# MHI-AC-Ctrl_v1_1.net
KiCad netlist of a schematic drawn in EAGLE
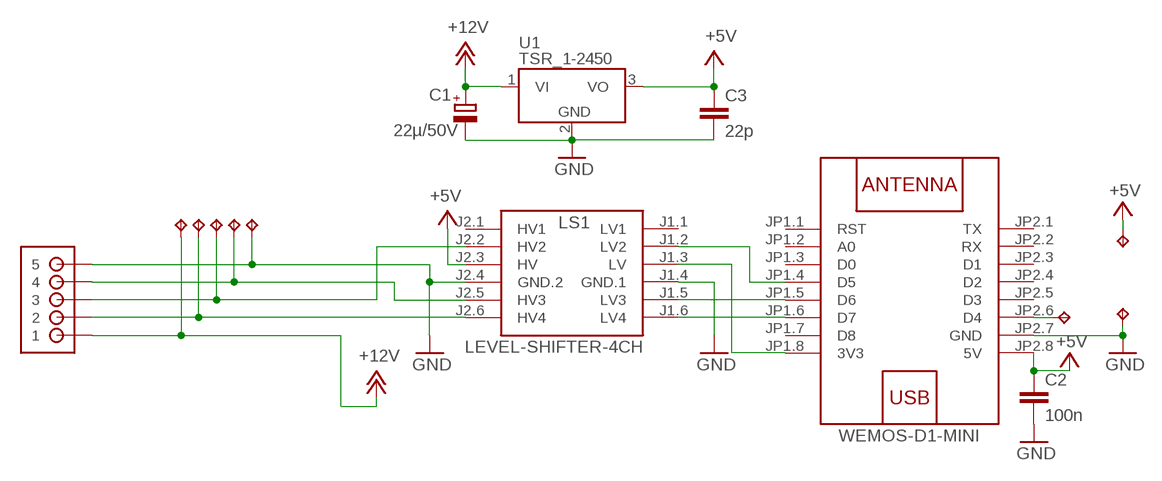
[diagram p0: schematic, sheet 1]

(export (version "E")
  (design (tool "Eeschema 10.0.6"))
  (components
    (comp (ref "C1")
      (value "22µ/50V")
      (footprint "eagle-import:E5-10,5")
      (libsource (lib "eagle-import") (part "CPOL-EUE5-10.5"))
    )
    (comp (ref "C2")
      (value "100n")
      (footprint "eagle-import:C025-024X044")
      (libsource (lib "eagle-import") (part "C-EU025-024X044"))
    )
    (comp (ref "C3")
      (value "22p")
      (footprint "eagle-import:C025-024X044")
      (libsource (lib "eagle-import") (part "C-EU025-024X044"))
    )
    (comp (ref "LS1")
      (value "LEVEL-SHIFTER-4CH")
      (footprint "eagle-import:LEVEL-SHIFTER-4CH")
      (libsource (lib "eagle-import") (part "LEVEL-SHIFTER-4CH"))
    )
    (comp (ref "TP6")
      (value "TPPAD1-13")
      (footprint "eagle-import:P1-13")
      (libsource (lib "eagle-import") (part "TPPAD1-13"))
    )
    (comp (ref "TP7")
      (value "TPPAD1-13")
      (footprint "eagle-import:P1-13")
      (libsource (lib "eagle-import") (part "TPPAD1-13"))
    )
    (comp (ref "TP8")
      (value "TPPAD1-13")
      (footprint "eagle-import:P1-13")
      (libsource (lib "eagle-import") (part "TPPAD1-13"))
    )
    (comp (ref "TP9")
      (value "TPPAD1-13")
      (footprint "eagle-import:P1-13")
      (libsource (lib "eagle-import") (part "TPPAD1-13"))
    )
    (comp (ref "TP10")
      (value "TPPAD1-13")
      (footprint "eagle-import:P1-13")
      (libsource (lib "eagle-import") (part "TPPAD1-13"))
    )
    (comp (ref "TP11")
      (value "TPPAD1-13")
      (footprint "eagle-import:P1-13")
      (libsource (lib "eagle-import") (part "TPPAD1-13"))
    )
    (comp (ref "TP12")
      (value "TPPAD1-13")
      (footprint "eagle-import:P1-13")
      (libsource (lib "eagle-import") (part "TPPAD1-13"))
    )
    (comp (ref "TP13")
      (value "TPPAD1-13")
      (footprint "eagle-import:P1-13")
      (libsource (lib "eagle-import") (part "TPPAD1-13"))
    )
    (comp (ref "U$1")
      (value "WEMOS-D1-MINI")
      (footprint "eagle-import:WEMOS-D1-MINI")
      (libsource (lib "eagle-import") (part "WEMOS-D1-MINI"))
    )
    (comp (ref "U$4")
      (value "JST-PH_5-PIN_HEADER")
      (footprint "eagle-import:JST_B5B-PH_HEADER")
      (libsource (lib "eagle-import") (part "JST-PH_5-PIN_HEADER"))
    )
    (comp (ref "U1")
      (value "TSR_1-2450")
      (footprint "eagle-import:TSR-1")
      (libsource (lib "eagle-import") (part "TSR_1-24_"))
    )
  )
  (nets
    (net (code "1") (name "+5V") (class "Default")
      (node (ref "C2") (pin "1") (pinfunction "1_1") (pintype "passive"))
      (node (ref "C3") (pin "1") (pinfunction "1_1") (pintype "passive"))
      (node (ref "LS1") (pin "J2.3") (pinfunction "HV_J2.3") (pintype "power_in"))
      (node (ref "TP8") (pin "TP") (pinfunction "TP_TP") (pintype "input"))
      (node (ref "U$1") (pin "JP2.8") (pinfunction "5V_JP2.8") (pintype "power_in"))
      (node (ref "U1") (pin "3") (pinfunction "VO_3") (pintype "power_in"))
    )
    (net (code "2") (name "+12V") (class "Default")
      (node (ref "C1") (pin "+") (pinfunction "+_+") (pintype "passive"))
      (node (ref "TP13") (pin "TP") (pinfunction "TP_TP") (pintype "input"))
      (node (ref "U$4") (pin "P1") (pinfunction "1_P1") (pintype "bidirectional"))
      (node (ref "U1") (pin "1") (pinfunction "VI_1") (pintype "power_in"))
    )
    (net (code "3") (name "GND") (class "Default")
      (node (ref "C1") (pin "-") (pinfunction "-_-") (pintype "passive"))
      (node (ref "C2") (pin "2") (pinfunction "2_2") (pintype "passive"))
      (node (ref "C3") (pin "2") (pinfunction "2_2") (pintype "passive"))
      (node (ref "LS1") (pin "J1.4") (pinfunction "GND.1_J1.4") (pintype "power_in"))
      (node (ref "LS1") (pin "J2.4") (pinfunction "GND.2_J2.4") (pintype "power_in"))
      (node (ref "TP7") (pin "TP") (pinfunction "TP_TP") (pintype "input"))
      (node (ref "TP9") (pin "TP") (pinfunction "TP_TP") (pintype "input"))
      (node (ref "U$1") (pin "JP2.7") (pinfunction "GND_JP2.7") (pintype "power_in"))
      (node (ref "U$4") (pin "P5") (pinfunction "5_P5") (pintype "bidirectional"))
      (node (ref "U1") (pin "2") (pinfunction "GND_2") (pintype "power_in"))
    )
    (net (code "4") (name "Net-(LS1-HV2)") (class "Default")
      (node (ref "LS1") (pin "J2.2") (pinfunction "HV2_J2.2") (pintype "bidirectional"))
      (node (ref "TP11") (pin "TP") (pinfunction "TP_TP") (pintype "input"))
      (node (ref "U$4") (pin "P3") (pinfunction "3_P3") (pintype "bidirectional"))
    )
    (net (code "5") (name "Net-(LS1-HV3)") (class "Default")
      (node (ref "LS1") (pin "J2.5") (pinfunction "HV3_J2.5") (pintype "bidirectional"))
      (node (ref "TP10") (pin "TP") (pinfunction "TP_TP") (pintype "input"))
      (node (ref "U$4") (pin "P4") (pinfunction "4_P4") (pintype "bidirectional"))
    )
    (net (code "6") (name "Net-(LS1-HV4)") (class "Default")
      (node (ref "LS1") (pin "J2.6") (pinfunction "HV4_J2.6") (pintype "bidirectional"))
      (node (ref "TP12") (pin "TP") (pinfunction "TP_TP") (pintype "input"))
      (node (ref "U$4") (pin "P2") (pinfunction "2_P2") (pintype "bidirectional"))
    )
    (net (code "7") (name "Net-(LS1-LV)") (class "Default")
      (node (ref "LS1") (pin "J1.3") (pinfunction "LV_J1.3") (pintype "power_in"))
      (node (ref "U$1") (pin "JP1.8") (pinfunction "3V3_JP1.8") (pintype "power_in"))
    )
    (net (code "8") (name "Net-(LS1-LV2)") (class "Default")
      (node (ref "LS1") (pin "J1.2") (pinfunction "LV2_J1.2") (pintype "bidirectional"))
      (node (ref "U$1") (pin "JP1.4") (pinfunction "D5_JP1.4") (pintype "bidirectional"))
    )
    (net (code "9") (name "Net-(LS1-LV3)") (class "Default")
      (node (ref "LS1") (pin "J1.5") (pinfunction "LV3_J1.5") (pintype "bidirectional"))
      (node (ref "U$1") (pin "JP1.5") (pinfunction "D6_JP1.5") (pintype "bidirectional"))
    )
    (net (code "10") (name "Net-(LS1-LV4)") (class "Default")
      (node (ref "LS1") (pin "J1.6") (pinfunction "LV4_J1.6") (pintype "bidirectional"))
      (node (ref "U$1") (pin "JP1.6") (pinfunction "D7_JP1.6") (pintype "bidirectional"))
    )
    (net (code "11") (name "Net-(U$1-D4)") (class "Default")
      (node (ref "TP6") (pin "TP") (pinfunction "TP_TP") (pintype "input"))
      (node (ref "U$1") (pin "JP2.6") (pinfunction "D4_JP2.6") (pintype "bidirectional"))
    )
    (net (code "12") (name "unconnected-(LS1-HV1-PadJ2.1)") (class "Default")
      (node (ref "LS1") (pin "J2.1") (pinfunction "HV1_J2.1") (pintype "bidirectional"))
    )
    (net (code "13") (name "unconnected-(LS1-LV1-PadJ1.1)") (class "Default")
      (node (ref "LS1") (pin "J1.1") (pinfunction "LV1_J1.1") (pintype "bidirectional"))
    )
    (net (code "14") (name "unconnected-(U$1-A0-PadJP1.2)") (class "Default")
      (node (ref "U$1") (pin "JP1.2") (pinfunction "A0_JP1.2") (pintype "bidirectional"))
    )
    (net (code "15") (name "unconnected-(U$1-D0-PadJP1.3)") (class "Default")
      (node (ref "U$1") (pin "JP1.3") (pinfunction "D0_JP1.3") (pintype "bidirectional"))
    )
    (net (code "16") (name "unconnected-(U$1-D1-PadJP2.3)") (class "Default")
      (node (ref "U$1") (pin "JP2.3") (pinfunction "D1_JP2.3") (pintype "bidirectional"))
    )
    (net (code "17") (name "unconnected-(U$1-D2-PadJP2.4)") (class "Default")
      (node (ref "U$1") (pin "JP2.4") (pinfunction "D2_JP2.4") (pintype "bidirectional"))
    )
    (net (code "18") (name "unconnected-(U$1-D3-PadJP2.5)") (class "Default")
      (node (ref "U$1") (pin "JP2.5") (pinfunction "D3_JP2.5") (pintype "bidirectional"))
    )
    (net (code "19") (name "unconnected-(U$1-D8-PadJP1.7)") (class "Default")
      (node (ref "U$1") (pin "JP1.7") (pinfunction "D8_JP1.7") (pintype "bidirectional"))
    )
    (net (code "20") (name "unconnected-(U$1-RST-PadJP1.1)") (class "Default")
      (node (ref "U$1") (pin "JP1.1") (pinfunction "RST_JP1.1") (pintype "bidirectional"))
    )
    (net (code "21") (name "unconnected-(U$1-RX-PadJP2.2)") (class "Default")
      (node (ref "U$1") (pin "JP2.2") (pinfunction "RX_JP2.2") (pintype "bidirectional"))
    )
    (net (code "22") (name "unconnected-(U$1-TX-PadJP2.1)") (class "Default")
      (node (ref "U$1") (pin "JP2.1") (pinfunction "TX_JP2.1") (pintype "bidirectional"))
    )
  )
)
